# 20210418-JGaylord-V2153M_DSheet.net
KiCad netlist of a schematic drawn in EAGLE
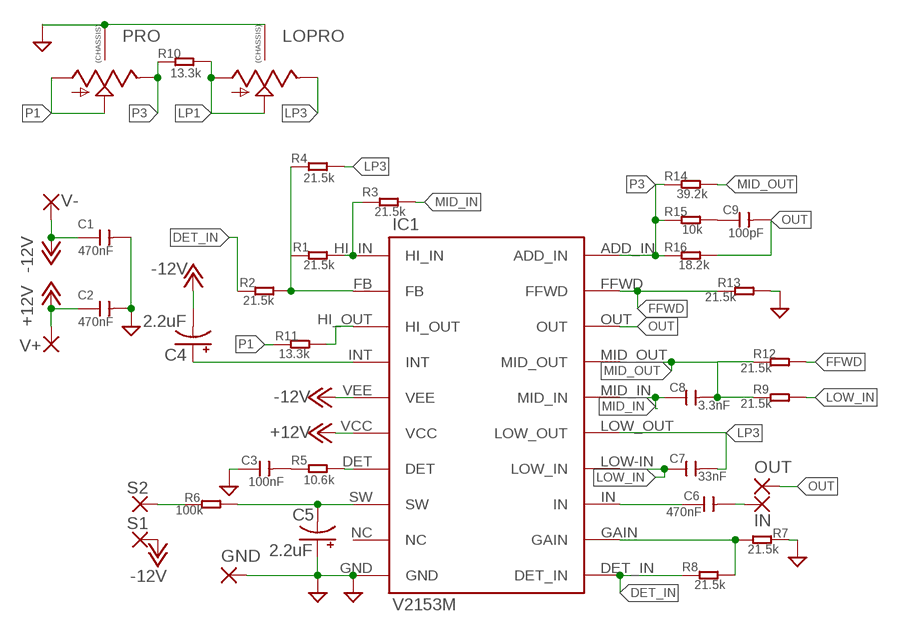
[diagram p0: schematic, sheet 1]

(export (version "E")
  (design (tool "Eeschema 10.0.6"))
  (components
    (comp (ref "C1")
      (value "470nF")
      (footprint "eagle-import:C0805")
      (fields (field (name "MPN") "CC0805KRX7R9BB104"))
      (libsource (lib "eagle-import") (part "CERAMIC-100NF-50V-10%-X7R(0805)"))
    )
    (comp (ref "C2")
      (value "470nF")
      (footprint "eagle-import:C0805")
      (fields (field (name "MPN") "CC0805KRX7R9BB104"))
      (libsource (lib "eagle-import") (part "CERAMIC-100NF-50V-10%-X7R(0805)"))
    )
    (comp (ref "C3")
      (value "100nF")
      (footprint "eagle-import:C0805")
      (fields (field (name "MPN") "CC0805KRX7R9BB104"))
      (libsource (lib "eagle-import") (part "CERAMIC-100NF-50V-10%-X7R(0805)"))
    )
    (comp (ref "C4")
      (value "2.2uF")
      (footprint "eagle-import:CAPMP3216X180N")
      (libsource (lib "eagle-import") (part "C-POL-USTANTALUM-1206(3216-METRIC)_"))
    )
    (comp (ref "C5")
      (value "2.2uF")
      (footprint "eagle-import:CAPMP3216X180N")
      (libsource (lib "eagle-import") (part "C-POL-USTANTALUM-1206(3216-METRIC)_"))
    )
    (comp (ref "C6")
      (value "470nF")
      (footprint "eagle-import:C0805")
      (fields (field (name "MPN") "CC0805KRX7R9BB104"))
      (libsource (lib "eagle-import") (part "CERAMIC-100NF-50V-10%-X7R(0805)"))
    )
    (comp (ref "C7")
      (value "33nF")
      (footprint "eagle-import:C0805")
      (fields (field (name "MPN") "CC0805KRX7R9BB104"))
      (libsource (lib "eagle-import") (part "CERAMIC-100NF-50V-10%-X7R(0805)"))
    )
    (comp (ref "C8")
      (value "3.3nF")
      (footprint "eagle-import:C0805")
      (fields (field (name "MPN") "CC0805KRX7R9BB104"))
      (libsource (lib "eagle-import") (part "CERAMIC-100NF-50V-10%-X7R(0805)"))
    )
    (comp (ref "C9")
      (value "100pF")
      (footprint "eagle-import:C0805")
      (fields (field (name "MPN") "CC0805KRX7R9BB104"))
      (libsource (lib "eagle-import") (part "CERAMIC-100NF-50V-10%-X7R(0805)"))
    )
    (comp (ref "GND")
      (value "WIREPAD1,6/0,9")
      (footprint "eagle-import:1,6_0,9")
      (libsource (lib "eagle-import") (part "WIREPAD1,6/0,9"))
    )
    (comp (ref "IC1")
      (value "V2153M")
      (footprint "eagle-import:V2153M")
      (libsource (lib "eagle-import") (part "V2153M"))
    )
    (comp (ref "IN")
      (value "WIREPAD1,6/0,9")
      (footprint "eagle-import:1,6_0,9")
      (libsource (lib "eagle-import") (part "WIREPAD1,6/0,9"))
    )
    (comp (ref "LOPRO")
      (value "9MM_SNAP-IN_POT_CHASSIS")
      (footprint "eagle-import:9MM_SNAP-IN_POT")
      (libsource (lib "eagle-import") (part "9MM_SNAP-IN_POT_CHASSIS"))
    )
    (comp (ref "OUT")
      (value "WIREPAD1,6/0,9")
      (footprint "eagle-import:1,6_0,9")
      (libsource (lib "eagle-import") (part "WIREPAD1,6/0,9"))
    )
    (comp (ref "PRO")
      (value "9MM_SNAP-IN_POT_CHASSIS")
      (footprint "eagle-import:9MM_SNAP-IN_POT")
      (libsource (lib "eagle-import") (part "9MM_SNAP-IN_POT_CHASSIS"))
    )
    (comp (ref "R1")
      (value "21.5k")
      (footprint "eagle-import:R0805")
      (fields (field (name "MPN") "RC0805JR-072K2L"))
      (libsource (lib "eagle-import") (part "SMD-RES-2.2K-5%-1/8W(0805)"))
    )
    (comp (ref "R2")
      (value "21.5k")
      (footprint "eagle-import:R0805")
      (fields (field (name "MPN") "RC0805JR-072K2L"))
      (libsource (lib "eagle-import") (part "SMD-RES-2.2K-5%-1/8W(0805)"))
    )
    (comp (ref "R3")
      (value "21.5k")
      (footprint "eagle-import:R0805")
      (fields (field (name "MPN") "RC0805JR-072K2L"))
      (libsource (lib "eagle-import") (part "SMD-RES-2.2K-5%-1/8W(0805)"))
    )
    (comp (ref "R4")
      (value "21.5k")
      (footprint "eagle-import:R0805")
      (fields (field (name "MPN") "RC0805JR-072K2L"))
      (libsource (lib "eagle-import") (part "SMD-RES-2.2K-5%-1/8W(0805)"))
    )
    (comp (ref "R5")
      (value "10.6k")
      (footprint "eagle-import:R0805")
      (fields (field (name "MPN") "RC0805JR-072K2L"))
      (libsource (lib "eagle-import") (part "SMD-RES-2.2K-5%-1/8W(0805)"))
    )
    (comp (ref "R6")
      (value "100k")
      (footprint "eagle-import:R0805")
      (fields (field (name "MPN") "RC0805JR-072K2L"))
      (libsource (lib "eagle-import") (part "SMD-RES-2.2K-5%-1/8W(0805)"))
    )
    (comp (ref "R7")
      (value "21.5k")
      (footprint "eagle-import:R0805")
      (fields (field (name "MPN") "RC0805JR-072K2L"))
      (libsource (lib "eagle-import") (part "SMD-RES-2.2K-5%-1/8W(0805)"))
    )
    (comp (ref "R8")
      (value "21.5k")
      (footprint "eagle-import:R0805")
      (fields (field (name "MPN") "RC0805JR-072K2L"))
      (libsource (lib "eagle-import") (part "SMD-RES-2.2K-5%-1/8W(0805)"))
    )
    (comp (ref "R9")
      (value "21.5k")
      (footprint "eagle-import:R0805")
      (fields (field (name "MPN") "RC0805JR-072K2L"))
      (libsource (lib "eagle-import") (part "SMD-RES-2.2K-5%-1/8W(0805)"))
    )
    (comp (ref "R10")
      (value "13.3k")
      (footprint "eagle-import:R0805")
      (fields (field (name "MPN") "RC0805JR-072K2L"))
      (libsource (lib "eagle-import") (part "SMD-RES-2.2K-5%-1/8W(0805)"))
    )
    (comp (ref "R11")
      (value "13.3k")
      (footprint "eagle-import:R0805")
      (fields (field (name "MPN") "RC0805JR-072K2L"))
      (libsource (lib "eagle-import") (part "SMD-RES-2.2K-5%-1/8W(0805)"))
    )
    (comp (ref "R12")
      (value "21.5k")
      (footprint "eagle-import:R0805")
      (fields (field (name "MPN") "RC0805JR-072K2L"))
      (libsource (lib "eagle-import") (part "SMD-RES-2.2K-5%-1/8W(0805)"))
    )
    (comp (ref "R13")
      (value "21.5k")
      (footprint "eagle-import:R0805")
      (fields (field (name "MPN") "RC0805JR-072K2L"))
      (libsource (lib "eagle-import") (part "SMD-RES-2.2K-5%-1/8W(0805)"))
    )
    (comp (ref "R14")
      (value "39.2k")
      (footprint "eagle-import:R0805")
      (fields (field (name "MPN") "RC0805JR-072K2L"))
      (libsource (lib "eagle-import") (part "SMD-RES-2.2K-5%-1/8W(0805)"))
    )
    (comp (ref "R15")
      (value "10k")
      (footprint "eagle-import:R0805")
      (fields (field (name "MPN") "RC0805JR-072K2L"))
      (libsource (lib "eagle-import") (part "SMD-RES-2.2K-5%-1/8W(0805)"))
    )
    (comp (ref "R16")
      (value "18.2k")
      (footprint "eagle-import:R0805")
      (fields (field (name "MPN") "RC0805JR-072K2L"))
      (libsource (lib "eagle-import") (part "SMD-RES-2.2K-5%-1/8W(0805)"))
    )
    (comp (ref "S1")
      (value "WIREPAD1,6/0,9")
      (footprint "eagle-import:1,6_0,9")
      (libsource (lib "eagle-import") (part "WIREPAD1,6/0,9"))
    )
    (comp (ref "S2")
      (value "WIREPAD1,6/0,9")
      (footprint "eagle-import:1,6_0,9")
      (libsource (lib "eagle-import") (part "WIREPAD1,6/0,9"))
    )
    (comp (ref "V+")
      (value "WIREPAD1,6/0,9")
      (footprint "eagle-import:1,6_0,9")
      (libsource (lib "eagle-import") (part "WIREPAD1,6/0,9"))
    )
    (comp (ref "V-")
      (value "WIREPAD1,6/0,9")
      (footprint "eagle-import:1,6_0,9")
      (libsource (lib "eagle-import") (part "WIREPAD1,6/0,9"))
    )
  )
  (nets
    (net (code "1") (name "+12V") (class "Default")
      (node (ref "C2") (pin "1") (pinfunction "1_1") (pintype "passive"))
      (node (ref "IC1") (pin "VCC") (pinfunction "VCC_VCC") (pintype "bidirectional"))
      (node (ref "V+") (pin "1") (pinfunction "P_1") (pintype "passive"))
    )
    (net (code "2") (name "-12V") (class "Default")
      (node (ref "C1") (pin "1") (pinfunction "1_1") (pintype "passive"))
      (node (ref "C4") (pin "2") (pinfunction "-_2") (pintype "passive"))
      (node (ref "IC1") (pin "VEE") (pinfunction "VEE_VEE") (pintype "bidirectional"))
      (node (ref "S1") (pin "1") (pinfunction "P_1") (pintype "passive"))
      (node (ref "V-") (pin "1") (pinfunction "P_1") (pintype "passive"))
    )
    (net (code "3") (name "DET_IN") (class "Default")
      (node (ref "IC1") (pin "DET_IN") (pinfunction "DET_IN_DET_IN") (pintype "bidirectional"))
      (node (ref "R2") (pin "1") (pinfunction "1_1") (pintype "passive"))
      (node (ref "R8") (pin "1") (pinfunction "1_1") (pintype "passive"))
    )
    (net (code "4") (name "FFWD") (class "Default")
      (node (ref "IC1") (pin "FFWD") (pinfunction "FFWD_FFWD") (pintype "bidirectional"))
      (node (ref "R12") (pin "2") (pinfunction "2_2") (pintype "passive"))
      (node (ref "R13") (pin "1") (pinfunction "1_1") (pintype "passive"))
    )
    (net (code "5") (name "GND") (class "Default")
      (node (ref "C1") (pin "2") (pinfunction "2_2") (pintype "passive"))
      (node (ref "C2") (pin "2") (pinfunction "2_2") (pintype "passive"))
      (node (ref "C3") (pin "1") (pinfunction "1_1") (pintype "passive"))
      (node (ref "C5") (pin "1") (pinfunction "+_1") (pintype "passive"))
      (node (ref "GND") (pin "1") (pinfunction "P_1") (pintype "passive"))
      (node (ref "IC1") (pin "GND") (pinfunction "GND_GND") (pintype "bidirectional"))
      (node (ref "LOPRO") (pin "CHASSIS1") (pinfunction "P$1_CHASSIS1") (pintype "passive"))
      (node (ref "LOPRO") (pin "CHASSIS2") (pinfunction "P$1_CHASSIS2") (pintype "passive"))
      (node (ref "PRO") (pin "CHASSIS1") (pinfunction "P$1_CHASSIS1") (pintype "passive"))
      (node (ref "PRO") (pin "CHASSIS2") (pinfunction "P$1_CHASSIS2") (pintype "passive"))
      (node (ref "R13") (pin "2") (pinfunction "2_2") (pintype "passive"))
      (node (ref "R7") (pin "2") (pinfunction "2_2") (pintype "passive"))
    )
    (net (code "6") (name "LOW_IN") (class "Default")
      (node (ref "C7") (pin "1") (pinfunction "1_1") (pintype "passive"))
      (node (ref "IC1") (pin "LOW-IN") (pinfunction "LOW_IN_LOW-IN") (pintype "bidirectional"))
      (node (ref "R9") (pin "2") (pinfunction "2_2") (pintype "passive"))
    )
    (net (code "7") (name "LP1") (class "Default")
      (node (ref "LOPRO") (pin "1") (pinfunction "A_1") (pintype "passive"))
      (node (ref "LOPRO") (pin "2") (pinfunction "S_2") (pintype "passive"))
      (node (ref "R10") (pin "2") (pinfunction "2_2") (pintype "passive"))
    )
    (net (code "8") (name "LP3") (class "Default")
      (node (ref "C7") (pin "2") (pinfunction "2_2") (pintype "passive"))
      (node (ref "IC1") (pin "LOW_OUT") (pinfunction "LOW_OUT_LOW_OUT") (pintype "bidirectional"))
      (node (ref "LOPRO") (pin "3") (pinfunction "E_3") (pintype "passive"))
      (node (ref "R4") (pin "2") (pinfunction "2_2") (pintype "passive"))
    )
    (net (code "9") (name "MID_IN") (class "Default")
      (node (ref "C8") (pin "1") (pinfunction "1_1") (pintype "passive"))
      (node (ref "IC1") (pin "MID_IN") (pinfunction "MID_IN_MID_IN") (pintype "bidirectional"))
      (node (ref "R3") (pin "2") (pinfunction "2_2") (pintype "passive"))
    )
    (net (code "10") (name "MID_OUT") (class "Default")
      (node (ref "C8") (pin "2") (pinfunction "2_2") (pintype "passive"))
      (node (ref "IC1") (pin "MID_OUT") (pinfunction "MID_OUT_MID_OUT") (pintype "bidirectional"))
      (node (ref "R12") (pin "1") (pinfunction "1_1") (pintype "passive"))
      (node (ref "R14") (pin "2") (pinfunction "2_2") (pintype "passive"))
      (node (ref "R9") (pin "1") (pinfunction "1_1") (pintype "passive"))
    )
    (net (code "11") (name "Net-(C3-Pad2)") (class "Default")
      (node (ref "C3") (pin "2") (pinfunction "2_2") (pintype "passive"))
      (node (ref "R5") (pin "1") (pinfunction "1_1") (pintype "passive"))
    )
    (net (code "12") (name "Net-(C4-+)") (class "Default")
      (node (ref "C4") (pin "1") (pinfunction "+_1") (pintype "passive"))
      (node (ref "IC1") (pin "INT") (pinfunction "INT_INT") (pintype "bidirectional"))
    )
    (net (code "13") (name "Net-(C5--)") (class "Default")
      (node (ref "C5") (pin "2") (pinfunction "-_2") (pintype "passive"))
      (node (ref "IC1") (pin "SW") (pinfunction "SW_SW") (pintype "bidirectional"))
      (node (ref "R6") (pin "2") (pinfunction "2_2") (pintype "passive"))
    )
    (net (code "14") (name "Net-(C6-Pad1)") (class "Default")
      (node (ref "C6") (pin "1") (pinfunction "1_1") (pintype "passive"))
      (node (ref "IC1") (pin "IN") (pinfunction "IN_IN") (pintype "bidirectional"))
    )
    (net (code "15") (name "Net-(C9-Pad1)") (class "Default")
      (node (ref "C9") (pin "1") (pinfunction "1_1") (pintype "passive"))
      (node (ref "R15") (pin "2") (pinfunction "2_2") (pintype "passive"))
    )
    (net (code "16") (name "Net-(IC1-PadDET)") (class "Default")
      (node (ref "IC1") (pin "DET") (pinfunction "DET_DET") (pintype "bidirectional"))
      (node (ref "R5") (pin "2") (pinfunction "2_2") (pintype "passive"))
    )
    (net (code "17") (name "Net-(IC1-PadFB)") (class "Default")
      (node (ref "IC1") (pin "FB") (pinfunction "FB_FB") (pintype "bidirectional"))
      (node (ref "R1") (pin "1") (pinfunction "1_1") (pintype "passive"))
      (node (ref "R2") (pin "2") (pinfunction "2_2") (pintype "passive"))
      (node (ref "R4") (pin "1") (pinfunction "1_1") (pintype "passive"))
    )
    (net (code "18") (name "Net-(IC1-PadGAIN)") (class "Default")
      (node (ref "IC1") (pin "GAIN") (pinfunction "GAIN_GAIN") (pintype "bidirectional"))
      (node (ref "R7") (pin "1") (pinfunction "1_1") (pintype "passive"))
      (node (ref "R8") (pin "2") (pinfunction "2_2") (pintype "passive"))
    )
    (net (code "19") (name "Net-(IC1-PadHI_IN)") (class "Default")
      (node (ref "IC1") (pin "HI_IN") (pinfunction "HI_IN_HI_IN") (pintype "bidirectional"))
      (node (ref "R1") (pin "2") (pinfunction "2_2") (pintype "passive"))
      (node (ref "R3") (pin "1") (pinfunction "1_1") (pintype "passive"))
    )
    (net (code "20") (name "Net-(IC1-PadHI_OUT)") (class "Default")
      (node (ref "IC1") (pin "HI_OUT") (pinfunction "HI_OUT_HI_OUT") (pintype "bidirectional"))
      (node (ref "R11") (pin "2") (pinfunction "2_2") (pintype "passive"))
    )
    (net (code "21") (name "Net-(IN-P)") (class "Default")
      (node (ref "C6") (pin "2") (pinfunction "2_2") (pintype "passive"))
      (node (ref "IN") (pin "1") (pinfunction "P_1") (pintype "passive"))
    )
    (net (code "22") (name "Net-(S2-P)") (class "Default")
      (node (ref "R6") (pin "1") (pinfunction "1_1") (pintype "passive"))
      (node (ref "S2") (pin "1") (pinfunction "P_1") (pintype "passive"))
    )
    (net (code "23") (name "OUT") (class "Default")
      (node (ref "C9") (pin "2") (pinfunction "2_2") (pintype "passive"))
      (node (ref "IC1") (pin "OUT") (pinfunction "OUT_OUT") (pintype "bidirectional"))
      (node (ref "OUT") (pin "1") (pinfunction "P_1") (pintype "passive"))
      (node (ref "R16") (pin "2") (pinfunction "2_2") (pintype "passive"))
    )
    (net (code "24") (name "P1") (class "Default")
      (node (ref "PRO") (pin "1") (pinfunction "A_1") (pintype "passive"))
      (node (ref "PRO") (pin "2") (pinfunction "S_2") (pintype "passive"))
      (node (ref "R11") (pin "1") (pinfunction "1_1") (pintype "passive"))
    )
    (net (code "25") (name "P3") (class "Default")
      (node (ref "IC1") (pin "ADD_IN") (pinfunction "ADD_IN_ADD_IN") (pintype "bidirectional"))
      (node (ref "PRO") (pin "3") (pinfunction "E_3") (pintype "passive"))
      (node (ref "R10") (pin "1") (pinfunction "1_1") (pintype "passive"))
      (node (ref "R14") (pin "1") (pinfunction "1_1") (pintype "passive"))
      (node (ref "R15") (pin "1") (pinfunction "1_1") (pintype "passive"))
      (node (ref "R16") (pin "1") (pinfunction "1_1") (pintype "passive"))
    )
    (net (code "26") (name "unconnected-(IC1-PadNC)") (class "Default")
      (node (ref "IC1") (pin "NC") (pinfunction "NC_NC") (pintype "bidirectional"))
    )
  )
)
